# Microccontroller.net
KiCad netlist of a schematic drawn in Altium Designer
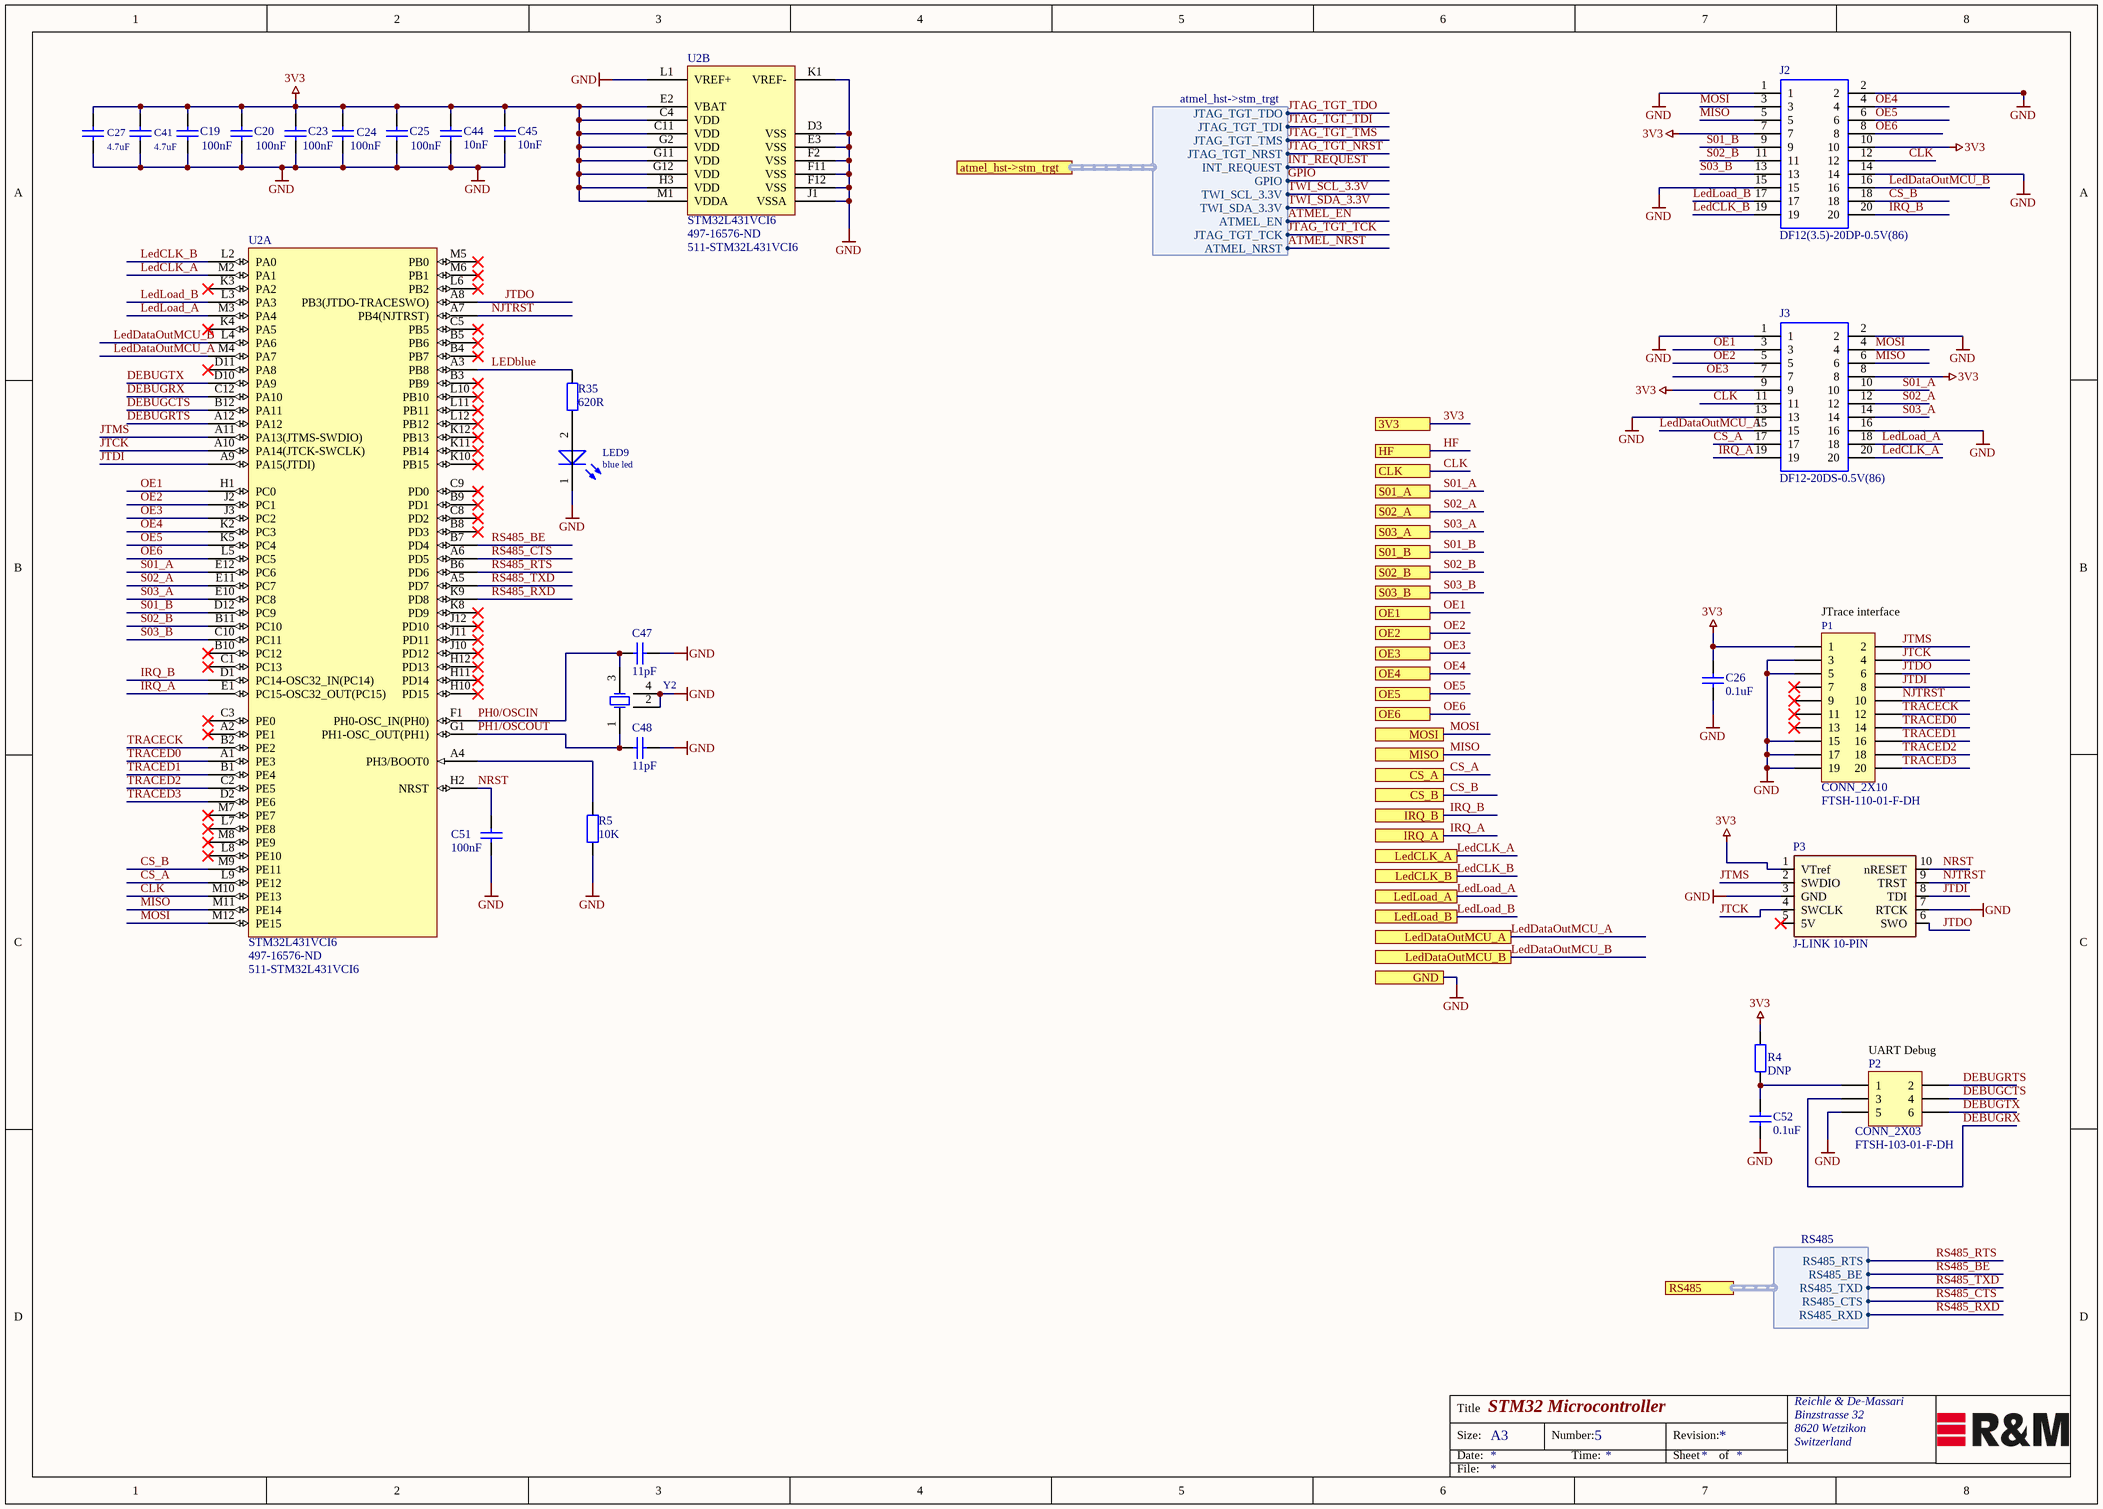
[diagram p0: Microccontroller.SchDoc]

(export (version "E")
  (design (tool "Eeschema 10.0.6"))
  (components
    (comp (ref "C19")
      (value "100nF")
      (footprint "CAPC0402(1005)60_L")
      (description "CAP 100nF 10V ±10% 0402 (1005 Metric) Thickness 0.6mm SMD")
      (fields (field (name "TOLERANCE") "Â±10%"))
      (libsource (lib "RDM_Altium_Library") (part "CAP 100nF 10V 0402(1005)"))
    )
    (comp (ref "C20")
      (value "100nF")
      (footprint "CAPC0402(1005)60_L")
      (description "CAP 100nF 10V ±10% 0402 (1005 Metric) Thickness 0.6mm SMD")
      (fields (field (name "TOLERANCE") "Â±10%"))
      (libsource (lib "RDM_Altium_Library") (part "CAP 100nF 10V 0402(1005)"))
    )
    (comp (ref "C23")
      (value "100nF")
      (footprint "CAPC0402(1005)60_L")
      (description "CAP 100nF 10V ±10% 0402 (1005 Metric) Thickness 0.6mm SMD")
      (fields (field (name "TOLERANCE") "Â±10%"))
      (libsource (lib "RDM_Altium_Library") (part "CAP 100nF 10V 0402(1005)"))
    )
    (comp (ref "C24")
      (value "100nF")
      (footprint "CAPC0402(1005)60_L")
      (description "CAP 100nF 10V ±10% 0402 (1005 Metric) Thickness 0.6mm SMD")
      (fields (field (name "TOLERANCE") "Â±10%"))
      (libsource (lib "RDM_Altium_Library") (part "CAP 100nF 10V 0402(1005)"))
    )
    (comp (ref "C25")
      (value "100nF")
      (footprint "CAPC0402(1005)60_L")
      (description "CAP 100nF 10V ±10% 0402 (1005 Metric) Thickness 0.6mm SMD")
      (fields (field (name "TOLERANCE") "Â±10%"))
      (libsource (lib "RDM_Altium_Library") (part "CAP 100nF 10V 0402(1005)"))
    )
    (comp (ref "C26")
      (value "0.1uF")
      (footprint "CAPC1005X55N")
      (description "SMD/SMT WCAP-CSGP 0.1uF 0402 20% 10V MLCC")
      (fields (field (name "TOLERANCE") "20%") (field (name "VOLTAGE") "10VDC"))
      (libsource (lib "RDM_Altium_Library") (part "Cap_0.1uF_0402"))
    )
    (comp (ref "C27")
      (value "4.7uF")
      (footprint "CAPC1005X55N")
      (description "4.7uF, Chip Monolithic Ceramic Condensators")
      (fields (field (name "MANUFACTURER") "Murata") (field (name "Comment") "DNP"))
      (libsource (lib "RDM_Altium_Library") (part "Cap_4.7uF_0402(1005)"))
    )
    (comp (ref "C41")
      (value "4.7uF")
      (footprint "CAP-0402[1005] - RFL")
      (description "4.7uF, Chip Monolithic Ceramic Condensators")
      (fields (field (name "MANUFACTURER") "Murata") (field (name "Comment") "GRM155R60J475ME47D"))
      (libsource (lib "RDM_Altium_Library") (part "Cap_4.7uF_0402(1005)"))
    )
    (comp (ref "C44")
      (value "10nF")
      (footprint "CAPC0402(1005)60_L")
      (description "CAP 10nF 10V ±10% 0402 (1005 Metric) Thickness 0.6mm SMD")
      (fields (field (name "TOLERANCE") "Â±10%"))
      (libsource (lib "RDM_Altium_Library") (part "CAP_10nf_10V_0402(1005)"))
    )
    (comp (ref "C45")
      (value "10nF")
      (footprint "CAPC0402(1005)60_L")
      (description "CAP 10nF 10V ±10% 0402 (1005 Metric) Thickness 0.6mm SMD")
      (fields (field (name "TOLERANCE") "Â±10%"))
      (libsource (lib "RDM_Altium_Library") (part "CAP_10nf_10V_0402(1005)"))
    )
    (comp (ref "C47")
      (value "11pF")
      (footprint "CAPC0402(1005)60_L")
      (description "CAP 11pF 10V ±0.25pF 0402 (1005 Metric) Thickness 0.6mm SMD")
      (fields (field (name "TOLERANCE") "Â±0.25pF"))
      (libsource (lib "RDM_Altium_Library") (part "CAP 11pF 10V 0402(1005)"))
    )
    (comp (ref "C48")
      (value "11pF")
      (footprint "CAPC0402(1005)60_L")
      (description "CAP 11pF 10V ±0.25pF 0402 (1005 Metric) Thickness 0.6mm SMD")
      (fields (field (name "TOLERANCE") "Â±0.25pF"))
      (libsource (lib "RDM_Altium_Library") (part "CAP 11pF 10V 0402(1005)"))
    )
    (comp (ref "C51")
      (value "100nF")
      (footprint "CAPC0402(1005)60_L")
      (description "CAP 100nF 10V ±10% 0402 (1005 Metric) Thickness 0.6mm SMD")
      (fields (field (name "TOLERANCE") "Â±10%"))
      (libsource (lib "RDM_Altium_Library") (part "CAP 100nF 10V 0402(1005)"))
    )
    (comp (ref "C52")
      (value "0.1uF")
      (footprint "Ceramic Capacitor 0402 EIA")
      (description "SMD/SMT WCAP-CSGP 0.1uF 0402 20% 10V MLCC")
      (fields (field (name "TOLERANCE") "20%") (field (name "VOLTAGE") "10VDC"))
      (libsource (lib "RDM_Altium_Library") (part "Cap_0.1uF_0402"))
    )
    (comp (ref "J2")
      (value "DF12(3.5)-20DP-0.5V(86)")
      (footprint "DF12(4.0)-20DP")
      (fields
        (field (name "MANUFACTURER") "Hirose")
        (field (name "RS PART NUMBER") "6082064P")
        (field (name "MOUSER PART NUMBER") "798-DF123520DP0.5V86")
      )
      (libsource (lib "RDM_Altium_Library") (part "DF12(3.5)-20DP-0.5V(86)"))
    )
    (comp (ref "J3")
      (value "DF12-20DS-0.5V(86)")
      (footprint "DF12-20DS")
      (fields
        (field (name "MANUFACTURER") "Hirose")
        (field (name "RS PART NUMBER") "1722478")
        (field (name "MOUSER PART NUMBER") "798-DF12-20DS-0.5V86")
      )
      (libsource (lib "RDM_Altium_Library") (part "DF12-20DS-0.5V(86)"))
    )
    (comp (ref "LED9")
      (value "blue led")
      (footprint "Kingbright_SMD_2_RWH")
      (description "blue, 1.6 x 0.6 mm Right Angle SMD Chip LED Lamp")
      (fields (field (name "MANUFACTURER") "Kingbright"))
      (libsource (lib "RDM_Altium_Library") (part "APA1606VBC/D"))
    )
    (comp (ref "P1")
      (value "CONN_2X10")
      (footprint "FTSH-110-01-F-DH")
      (description "20Pin, 2Rows, side/horizontally, MICRO LOW-PROFILE TERMINAL STRIPS")
      (fields (field (name "MANUFACTURER") "Samtec") (field (name "MANUFACTURER PARTNR") "FTSH-110-01-F-DH"))
      (libsource (lib "RDM_Altium_Library") (part "CONN_2X10_FTSH-110-01-F-DH"))
    )
    (comp (ref "P2")
      (value "CONN_2X03")
      (footprint "FTSH-103-01-F-DH")
      (description "6Pin, 2Rows, MICRO LOW-PROFILE TERMINAL STRIPS")
      (fields (field (name "MANUFACTURER") "Samtec") (field (name "MANUFACTURER PARTNR") "FTSH-103-01-F-DH"))
      (libsource (lib "RDM_Altium_Library") (part "CONN_2X03_FTSH-103-01-F-DH"))
    )
    (comp (ref "P3")
      (value "J-LINK 10-PIN")
      (footprint "CONN-SEGGER-10-PIN")
      (description "Segger, J-Link 10-pin Needle Adapter")
      (libsource (lib "RDM_ALT_SCH") (part "CONN_Segger_10_PIN"))
    )
    (comp (ref "R4")
      (value "DNP")
      (footprint "RESC1005X40N")
      (description "Resistor: do not populate")
      (fields (field (name "MANUFACTURER") "do not populate"))
      (libsource (lib "RDM_Altium_Library") (part "Res_DNP_0402"))
    )
    (comp (ref "R5")
      (value "10K")
      (footprint "RESC1005X40N")
      (description "10K 0.063W 1% 0402 (1005 Metric)  SMD")
      (libsource (lib "RDM_Altium_Library") (part "PassResBas0402-00623-A.3"))
    )
    (comp (ref "R35")
      (value "620R")
      (footprint "Resistor 0402 EIA")
      (description "SMD 1/16W 620ohm 0.5% 25ppm")
      (fields (field (name "TOLERANCE") "0.5%") (field (name "POWER") "62.5mW"))
      (libsource (lib "RDM_Altium_Library") (part "Res_620R_0402"))
    )
    (comp (ref "U2")
      (value "STM32L431VCI6")
      (footprint "STM_UFBGA100 7x7x0.6_100_R")
      (fields
        (field (name "MANUFACTURER") "STMicroelectronics")
        (field (name "SUPPLIER PART NUMBER 1") "497-16576-ND")
        (field (name "SUPPLIER PART NUMBER 2") "511-STM32L431VCI6")
      )
      (libsource (lib "RDM_Altium_Library") (part "STM32L431VCI6"))
    )
    (comp (ref "Y2")
      (value "ECS-160-10-36Q-ES-TR")
      (footprint "ECS_ECX-2236_4_R")
      (description "48MHz, SMD CRYSTAL")
      (fields (field (name "MANUFACTURER") "ECS"))
      (libsource (lib "RDM_Altium_Library") (part "CRYSTAL_4Pin_1_3"))
    )
  )
  (nets
    (net (code "5") (name "/CLK") (class "Default")
      (node (ref "J2") (pin "12") (pinfunction "12_12") (pintype "passive"))
      (node (ref "J3") (pin "11") (pinfunction "11_11") (pintype "passive"))
      (node (ref "U2") (pin "M10") (pinfunction "PE13_M10") (pintype "bidirectional"))
    )
    (net (code "6") (name "/CS_A") (class "Default")
      (node (ref "J3") (pin "17") (pinfunction "17_17") (pintype "passive"))
      (node (ref "U2") (pin "L9") (pinfunction "PE12_L9") (pintype "bidirectional"))
    )
    (net (code "7") (name "/CS_B") (class "Default")
      (node (ref "J2") (pin "18") (pinfunction "18_18") (pintype "passive"))
      (node (ref "U2") (pin "M9") (pinfunction "PE11_M9") (pintype "bidirectional"))
    )
    (net (code "8") (name "/DEBUGCTS") (class "Default")
      (node (ref "P2") (pin "4") (pinfunction "4_4") (pintype "passive"))
      (node (ref "U2") (pin "B12") (pinfunction "PA11_B12") (pintype "bidirectional"))
    )
    (net (code "9") (name "/DEBUGRTS") (class "Default")
      (node (ref "P2") (pin "2") (pinfunction "2_2") (pintype "passive"))
      (node (ref "U2") (pin "A12") (pinfunction "PA12_A12") (pintype "bidirectional"))
    )
    (net (code "10") (name "/DEBUGRX") (class "Default")
      (node (ref "P2") (pin "3") (pinfunction "3_3") (pintype "passive"))
      (node (ref "U2") (pin "C12") (pinfunction "PA10_C12") (pintype "bidirectional"))
    )
    (net (code "11") (name "/DEBUGTX") (class "Default")
      (node (ref "P2") (pin "6") (pinfunction "6_6") (pintype "passive"))
      (node (ref "U2") (pin "D10") (pinfunction "PA9_D10") (pintype "bidirectional"))
    )
    (net (code "15") (name "/IRQ_A") (class "Default")
      (node (ref "J3") (pin "19") (pinfunction "19_19") (pintype "passive"))
      (node (ref "U2") (pin "E1") (pinfunction "PC15-OSC32_OUT(PC15)_E1") (pintype "bidirectional"))
    )
    (net (code "16") (name "/IRQ_B") (class "Default")
      (node (ref "J2") (pin "20") (pinfunction "20_20") (pintype "passive"))
      (node (ref "U2") (pin "D1") (pinfunction "PC14-OSC32_IN(PC14)_D1") (pintype "bidirectional"))
    )
    (net (code "22") (name "/JTCK") (class "Default")
      (node (ref "P1") (pin "4") (pinfunction "4_4") (pintype "passive"))
      (node (ref "P3") (pin "4") (pinfunction "SWCLK_4") (pintype "passive"))
      (node (ref "U2") (pin "A10") (pinfunction "PA14(JTCK-SWCLK)_A10") (pintype "bidirectional"))
    )
    (net (code "23") (name "/JTDI") (class "Default")
      (node (ref "P1") (pin "8") (pinfunction "8_8") (pintype "passive"))
      (node (ref "P3") (pin "8") (pinfunction "TDI_8") (pintype "passive"))
      (node (ref "U2") (pin "A9") (pinfunction "PA15(JTDI)_A9") (pintype "bidirectional"))
    )
    (net (code "24") (name "/JTDO") (class "Default")
      (node (ref "P1") (pin "6") (pinfunction "6_6") (pintype "passive"))
      (node (ref "P3") (pin "6") (pinfunction "SWO_6") (pintype "passive"))
      (node (ref "U2") (pin "A8") (pinfunction "PB3(JTDO-TRACESWO)_A8") (pintype "bidirectional"))
    )
    (net (code "25") (name "/JTMS") (class "Default")
      (node (ref "P1") (pin "2") (pinfunction "2_2") (pintype "passive"))
      (node (ref "P3") (pin "2") (pinfunction "SWDIO_2") (pintype "passive"))
      (node (ref "U2") (pin "A11") (pinfunction "PA13(JTMS-SWDIO)_A11") (pintype "bidirectional"))
    )
    (net (code "26") (name "/LEDblue") (class "Default")
      (node (ref "R35") (pin "2") (pinfunction "2_2") (pintype "passive"))
      (node (ref "U2") (pin "A3") (pinfunction "PB8_A3") (pintype "bidirectional"))
    )
    (net (code "27") (name "/LedCLK_A") (class "Default")
      (node (ref "J3") (pin "20") (pinfunction "20_20") (pintype "passive"))
      (node (ref "U2") (pin "M2") (pinfunction "PA1_M2") (pintype "bidirectional"))
    )
    (net (code "28") (name "/LedCLK_B") (class "Default")
      (node (ref "J2") (pin "19") (pinfunction "19_19") (pintype "passive"))
      (node (ref "U2") (pin "L2") (pinfunction "PA0_L2") (pintype "bidirectional"))
    )
    (net (code "29") (name "/LedDataOutMCU_A") (class "Default")
      (node (ref "J3") (pin "15") (pinfunction "15_15") (pintype "passive"))
      (node (ref "U2") (pin "M4") (pinfunction "PA7_M4") (pintype "bidirectional"))
    )
    (net (code "30") (name "/LedDataOutMCU_B") (class "Default")
      (node (ref "J2") (pin "16") (pinfunction "16_16") (pintype "passive"))
      (node (ref "U2") (pin "L4") (pinfunction "PA6_L4") (pintype "bidirectional"))
    )
    (net (code "31") (name "/LedLoad_A") (class "Default")
      (node (ref "J3") (pin "18") (pinfunction "18_18") (pintype "passive"))
      (node (ref "U2") (pin "M3") (pinfunction "PA4_M3") (pintype "bidirectional"))
    )
    (net (code "32") (name "/LedLoad_B") (class "Default")
      (node (ref "J2") (pin "17") (pinfunction "17_17") (pintype "passive"))
      (node (ref "U2") (pin "L3") (pinfunction "PA3_L3") (pintype "bidirectional"))
    )
    (net (code "33") (name "/MISO") (class "Default")
      (node (ref "J2") (pin "5") (pinfunction "5_5") (pintype "passive"))
      (node (ref "J3") (pin "6") (pinfunction "6_6") (pintype "passive"))
      (node (ref "U2") (pin "M11") (pinfunction "PE14_M11") (pintype "bidirectional"))
    )
    (net (code "34") (name "/MOSI") (class "Default")
      (node (ref "J2") (pin "3") (pinfunction "3_3") (pintype "passive"))
      (node (ref "J3") (pin "4") (pinfunction "4_4") (pintype "passive"))
      (node (ref "U2") (pin "M12") (pinfunction "PE15_M12") (pintype "bidirectional"))
    )
    (net (code "35") (name "/NJTRST") (class "Default")
      (node (ref "P1") (pin "10") (pinfunction "10_10") (pintype "passive"))
      (node (ref "P3") (pin "9") (pinfunction "TRST_9") (pintype "passive"))
      (node (ref "U2") (pin "A7") (pinfunction "PB4(NJTRST)_A7") (pintype "bidirectional"))
    )
    (net (code "36") (name "/NRST") (class "Default")
      (node (ref "C51") (pin "2") (pinfunction "2_2") (pintype "passive"))
      (node (ref "P3") (pin "10") (pinfunction "nRESET_10") (pintype "passive"))
      (node (ref "U2") (pin "H2") (pinfunction "NRST_H2") (pintype "bidirectional"))
    )
    (net (code "37") (name "/OE1") (class "Default")
      (node (ref "J3") (pin "3") (pinfunction "3_3") (pintype "passive"))
      (node (ref "U2") (pin "H1") (pinfunction "PC0_H1") (pintype "bidirectional"))
    )
    (net (code "38") (name "/OE2") (class "Default")
      (node (ref "J3") (pin "5") (pinfunction "5_5") (pintype "passive"))
      (node (ref "U2") (pin "J2") (pinfunction "PC1_J2") (pintype "bidirectional"))
    )
    (net (code "39") (name "/OE3") (class "Default")
      (node (ref "J3") (pin "7") (pinfunction "7_7") (pintype "passive"))
      (node (ref "U2") (pin "J3") (pinfunction "PC2_J3") (pintype "bidirectional"))
    )
    (net (code "40") (name "/OE4") (class "Default")
      (node (ref "J2") (pin "4") (pinfunction "4_4") (pintype "passive"))
      (node (ref "U2") (pin "K2") (pinfunction "PC3_K2") (pintype "bidirectional"))
    )
    (net (code "41") (name "/OE5") (class "Default")
      (node (ref "J2") (pin "6") (pinfunction "6_6") (pintype "passive"))
      (node (ref "U2") (pin "K5") (pinfunction "PC4_K5") (pintype "bidirectional"))
    )
    (net (code "42") (name "/OE6") (class "Default")
      (node (ref "J2") (pin "8") (pinfunction "8_8") (pintype "passive"))
      (node (ref "U2") (pin "L5") (pinfunction "PC5_L5") (pintype "bidirectional"))
    )
    (net (code "43") (name "/PH0{slash}OSCIN") (class "Default")
      (node (ref "C47") (pin "1") (pinfunction "1_1") (pintype "passive"))
      (node (ref "U2") (pin "F1") (pinfunction "PH0-OSC_IN(PH0)_F1") (pintype "bidirectional"))
      (node (ref "Y2") (pin "3") (pinfunction "OSC2_3") (pintype "passive"))
    )
    (net (code "44") (name "/PH1{slash}OSCOUT") (class "Default")
      (node (ref "C48") (pin "1") (pinfunction "1_1") (pintype "passive"))
      (node (ref "U2") (pin "G1") (pinfunction "PH1-OSC_OUT(PH1)_G1") (pintype "bidirectional"))
      (node (ref "Y2") (pin "1") (pinfunction "OSC1_1") (pintype "passive"))
    )
    (net (code "45") (name "/RS485_BE") (class "Default")
      (node (ref "U2") (pin "B7") (pinfunction "PD4_B7") (pintype "bidirectional"))
    )
    (net (code "46") (name "/RS485_CTS") (class "Default")
      (node (ref "U2") (pin "A6") (pinfunction "PD5_A6") (pintype "bidirectional"))
    )
    (net (code "47") (name "/RS485_RTS") (class "Default")
      (node (ref "U2") (pin "B6") (pinfunction "PD6_B6") (pintype "bidirectional"))
    )
    (net (code "48") (name "/RS485_RXD") (class "Default")
      (node (ref "U2") (pin "K9") (pinfunction "PD8_K9") (pintype "bidirectional"))
    )
    (net (code "49") (name "/RS485_TXD") (class "Default")
      (node (ref "U2") (pin "A5") (pinfunction "PD7_A5") (pintype "bidirectional"))
    )
    (net (code "50") (name "/S01_A") (class "Default")
      (node (ref "J3") (pin "10") (pinfunction "10_10") (pintype "passive"))
      (node (ref "U2") (pin "E12") (pinfunction "PC6_E12") (pintype "bidirectional"))
    )
    (net (code "51") (name "/S01_B") (class "Default")
      (node (ref "J2") (pin "9") (pinfunction "9_9") (pintype "passive"))
      (node (ref "U2") (pin "D12") (pinfunction "PC9_D12") (pintype "bidirectional"))
    )
    (net (code "52") (name "/S02_A") (class "Default")
      (node (ref "J3") (pin "12") (pinfunction "12_12") (pintype "passive"))
      (node (ref "U2") (pin "E11") (pinfunction "PC7_E11") (pintype "bidirectional"))
    )
    (net (code "53") (name "/S02_B") (class "Default")
      (node (ref "J2") (pin "11") (pinfunction "11_11") (pintype "passive"))
      (node (ref "U2") (pin "B11") (pinfunction "PC10_B11") (pintype "bidirectional"))
    )
    (net (code "54") (name "/S03_A") (class "Default")
      (node (ref "J3") (pin "14") (pinfunction "14_14") (pintype "passive"))
      (node (ref "U2") (pin "E10") (pinfunction "PC8_E10") (pintype "bidirectional"))
    )
    (net (code "55") (name "/S03_B") (class "Default")
      (node (ref "J2") (pin "13") (pinfunction "13_13") (pintype "passive"))
      (node (ref "U2") (pin "C10") (pinfunction "PC11_C10") (pintype "bidirectional"))
    )
    (net (code "56") (name "/TRACECK") (class "Default")
      (node (ref "P1") (pin "12") (pinfunction "12_12") (pintype "passive"))
      (node (ref "U2") (pin "B2") (pinfunction "PE2_B2") (pintype "bidirectional"))
    )
    (net (code "57") (name "/TRACED0") (class "Default")
      (node (ref "P1") (pin "14") (pinfunction "14_14") (pintype "passive"))
      (node (ref "U2") (pin "A1") (pinfunction "PE3_A1") (pintype "bidirectional"))
    )
    (net (code "58") (name "/TRACED1") (class "Default")
      (node (ref "P1") (pin "16") (pinfunction "16_16") (pintype "passive"))
      (node (ref "U2") (pin "B1") (pinfunction "PE4_B1") (pintype "bidirectional"))
    )
    (net (code "59") (name "/TRACED2") (class "Default")
      (node (ref "P1") (pin "18") (pinfunction "18_18") (pintype "passive"))
      (node (ref "U2") (pin "C2") (pinfunction "PE5_C2") (pintype "bidirectional"))
    )
    (net (code "60") (name "/TRACED3") (class "Default")
      (node (ref "P1") (pin "20") (pinfunction "20_20") (pintype "passive"))
      (node (ref "U2") (pin "D2") (pinfunction "PE6_D2") (pintype "bidirectional"))
    )
    (net (code "65") (name "3V3") (class "Default")
      (node (ref "C19") (pin "2") (pinfunction "2_2") (pintype "passive"))
      (node (ref "C20") (pin "2") (pinfunction "2_2") (pintype "passive"))
      (node (ref "C23") (pin "2") (pinfunction "2_2") (pintype "passive"))
      (node (ref "C24") (pin "2") (pinfunction "2_2") (pintype "passive"))
      (node (ref "C25") (pin "2") (pinfunction "2_2") (pintype "passive"))
      (node (ref "C26") (pin "2") (pinfunction "2_2") (pintype "passive"))
      (node (ref "C27") (pin "1") (pinfunction "Pos_1") (pintype "passive"))
      (node (ref "C41") (pin "1") (pinfunction "Pos_1") (pintype "passive"))
      (node (ref "C44") (pin "2") (pinfunction "2_2") (pintype "passive"))
      (node (ref "C45") (pin "2") (pinfunction "2_2") (pintype "passive"))
      (node (ref "J2") (pin "10") (pinfunction "10_10") (pintype "passive"))
      (node (ref "J2") (pin "7") (pinfunction "7_7") (pintype "passive"))
      (node (ref "J3") (pin "8") (pinfunction "8_8") (pintype "passive"))
      (node (ref "J3") (pin "9") (pinfunction "9_9") (pintype "passive"))
      (node (ref "P1") (pin "1") (pinfunction "1_1") (pintype "passive"))
      (node (ref "P3") (pin "1") (pinfunction "VTref_1") (pintype "passive"))
      (node (ref "R4") (pin "2") (pinfunction "2_2") (pintype "passive"))
      (node (ref "U2") (pin "C11") (pinfunction "VDD_C11") (pintype "power_in"))
      (node (ref "U2") (pin "C4") (pinfunction "VDD_C4") (pintype "power_in"))
      (node (ref "U2") (pin "E2") (pinfunction "VBAT_E2") (pintype "power_in"))
      (node (ref "U2") (pin "G11") (pinfunction "VDD_G11") (pintype "power_in"))
      (node (ref "U2") (pin "G12") (pinfunction "VDD_G12") (pintype "power_in"))
      (node (ref "U2") (pin "G2") (pinfunction "VDD_G2") (pintype "power_in"))
      (node (ref "U2") (pin "H3") (pinfunction "VDD_H3") (pintype "power_in"))
      (node (ref "U2") (pin "M1") (pinfunction "VDDA_M1") (pintype "power_in"))
    )
    (net (code "66") (name "GND") (class "Default")
      (node (ref "C19") (pin "1") (pinfunction "1_1") (pintype "passive"))
      (node (ref "C20") (pin "1") (pinfunction "1_1") (pintype "passive"))
      (node (ref "C23") (pin "1") (pinfunction "1_1") (pintype "passive"))
      (node (ref "C24") (pin "1") (pinfunction "1_1") (pintype "passive"))
      (node (ref "C25") (pin "1") (pinfunction "1_1") (pintype "passive"))
      (node (ref "C26") (pin "1") (pinfunction "1_1") (pintype "passive"))
      (node (ref "C27") (pin "2") (pinfunction "Neg_2") (pintype "passive"))
      (node (ref "C41") (pin "2") (pinfunction "Neg_2") (pintype "passive"))
      (node (ref "C44") (pin "1") (pinfunction "1_1") (pintype "passive"))
      (node (ref "C45") (pin "1") (pinfunction "1_1") (pintype "passive"))
      (node (ref "C47") (pin "2") (pinfunction "2_2") (pintype "passive"))
      (node (ref "C48") (pin "2") (pinfunction "2_2") (pintype "passive"))
      (node (ref "C51") (pin "1") (pinfunction "1_1") (pintype "passive"))
      (node (ref "C52") (pin "1") (pinfunction "1_1") (pintype "passive"))
      (node (ref "J2") (pin "1") (pinfunction "1_1") (pintype "passive"))
      (node (ref "J2") (pin "14") (pinfunction "14_14") (pintype "passive"))
      (node (ref "J2") (pin "15") (pinfunction "15_15") (pintype "passive"))
      (node (ref "J2") (pin "2") (pinfunction "2_2") (pintype "passive"))
      (node (ref "J3") (pin "1") (pinfunction "1_1") (pintype "passive"))
      (node (ref "J3") (pin "13") (pinfunction "13_13") (pintype "passive"))
      (node (ref "J3") (pin "16") (pinfunction "16_16") (pintype "passive"))
      (node (ref "J3") (pin "2") (pinfunction "2_2") (pintype "passive"))
      (node (ref "LED9") (pin "1") (pinfunction "K_1") (pintype "passive"))
      (node (ref "P1") (pin "15") (pinfunction "15_15") (pintype "passive"))
      (node (ref "P1") (pin "17") (pinfunction "17_17") (pintype "passive"))
      (node (ref "P1") (pin "19") (pinfunction "19_19") (pintype "passive"))
      (node (ref "P1") (pin "3") (pinfunction "3_3") (pintype "passive"))
      (node (ref "P1") (pin "5") (pinfunction "5_5") (pintype "passive"))
      (node (ref "P2") (pin "5") (pinfunction "5_5") (pintype "passive"))
      (node (ref "P3") (pin "3") (pinfunction "GND_3") (pintype "passive"))
      (node (ref "P3") (pin "7") (pinfunction "RTCK_7") (pintype "passive"))
      (node (ref "R5") (pin "2") (pinfunction "2_2") (pintype "passive"))
      (node (ref "U2") (pin "D3") (pinfunction "VSS_D3") (pintype "power_in"))
      (node (ref "U2") (pin "E3") (pinfunction "VSS_E3") (pintype "power_in"))
      (node (ref "U2") (pin "F11") (pinfunction "VSS_F11") (pintype "power_in"))
      (node (ref "U2") (pin "F12") (pinfunction "VSS_F12") (pintype "power_in"))
      (node (ref "U2") (pin "F2") (pinfunction "VSS_F2") (pintype "power_in"))
      (node (ref "U2") (pin "J1") (pinfunction "VSSA_J1") (pintype "power_in"))
      (node (ref "U2") (pin "K1") (pinfunction "VREF-_K1") (pintype "power_in"))
      (node (ref "U2") (pin "L1") (pinfunction "VREF+_L1") (pintype "power_in"))
      (node (ref "Y2") (pin "2") (pinfunction "OSC2_2") (pintype "passive"))
      (node (ref "Y2") (pin "4") (pinfunction "OSC3_4") (pintype "passive"))
    )
    (net (code "67") (name "Net-(C52-Pad2)") (class "Default")
      (node (ref "C52") (pin "2") (pinfunction "2_2") (pintype "passive"))
      (node (ref "P2") (pin "1") (pinfunction "1_1") (pintype "passive"))
      (node (ref "R4") (pin "1") (pinfunction "1_1") (pintype "passive"))
    )
    (net (code "68") (name "Net-(LED9-A)") (class "Default")
      (node (ref "LED9") (pin "2") (pinfunction "A_2") (pintype "passive"))
      (node (ref "R35") (pin "1") (pinfunction "1_1") (pintype "passive"))
    )
    (net (code "69") (name "Net-(U2A-PH3{slash}BOOT0)") (class "Default")
      (node (ref "R5") (pin "1") (pinfunction "1_1") (pintype "passive"))
      (node (ref "U2") (pin "A4") (pinfunction "PH3/BOOT0_A4") (pintype "input"))
    )
    (net (code "70") (name "unconnected-(P1-Pad7)") (class "Default")
      (node (ref "P1") (pin "7") (pinfunction "7_7") (pintype "passive+no_connect"))
    )
    (net (code "71") (name "unconnected-(P1-Pad9)") (class "Default")
      (node (ref "P1") (pin "9") (pinfunction "9_9") (pintype "passive+no_connect"))
    )
    (net (code "72") (name "unconnected-(P1-Pad11)") (class "Default")
      (node (ref "P1") (pin "11") (pinfunction "11_11") (pintype "passive+no_connect"))
    )
    (net (code "73") (name "unconnected-(P1-Pad13)") (class "Default")
      (node (ref "P1") (pin "13") (pinfunction "13_13") (pintype "passive+no_connect"))
    )
    (net (code "74") (name "unconnected-(P3-5V-Pad5)") (class "Default")
      (node (ref "P3") (pin "5") (pinfunction "5V_5") (pintype "passive+no_connect"))
    )
    (net (code "75") (name "unconnected-(U2A-PA2-PadK3)") (class "Default")
      (node (ref "U2") (pin "K3") (pinfunction "PA2_K3") (pintype "bidirectional+no_connect"))
    )
    (net (code "76") (name "unconnected-(U2A-PA5-PadK4)") (class "Default")
      (node (ref "U2") (pin "K4") (pinfunction "PA5_K4") (pintype "bidirectional+no_connect"))
    )
    (net (code "77") (name "unconnected-(U2A-PA8-PadD11)") (class "Default")
      (node (ref "U2") (pin "D11") (pinfunction "PA8_D11") (pintype "bidirectional+no_connect"))
    )
    (net (code "78") (name "unconnected-(U2A-PB0-PadM5)") (class "Default")
      (node (ref "U2") (pin "M5") (pinfunction "PB0_M5") (pintype "bidirectional+no_connect"))
    )
    (net (code "79") (name "unconnected-(U2A-PB1-PadM6)") (class "Default")
      (node (ref "U2") (pin "M6") (pinfunction "PB1_M6") (pintype "bidirectional+no_connect"))
    )
    (net (code "80") (name "unconnected-(U2A-PB2-PadL6)") (class "Default")
      (node (ref "U2") (pin "L6") (pinfunction "PB2_L6") (pintype "bidirectional+no_connect"))
    )
    (net (code "81") (name "unconnected-(U2A-PB5-PadC5)") (class "Default")
      (node (ref "U2") (pin "C5") (pinfunction "PB5_C5") (pintype "bidirectional+no_connect"))
    )
    (net (code "82") (name "unconnected-(U2A-PB6-PadB5)") (class "Default")
      (node (ref "U2") (pin "B5") (pinfunction "PB6_B5") (pintype "bidirectional+no_connect"))
    )
    (net (code "83") (name "unconnected-(U2A-PB7-PadB4)") (class "Default")
      (node (ref "U2") (pin "B4") (pinfunction "PB7_B4") (pintype "bidirectional+no_connect"))
    )
    (net (code "84") (name "unconnected-(U2A-PB9-PadB3)") (class "Default")
      (node (ref "U2") (pin "B3") (pinfunction "PB9_B3") (pintype "bidirectional+no_connect"))
    )
    (net (code "85") (name "unconnected-(U2A-PB10-PadL10)") (class "Default")
      (node (ref "U2") (pin "L10") (pinfunction "PB10_L10") (pintype "bidirectional+no_connect"))
    )
    (net (code "86") (name "unconnected-(U2A-PB11-PadL11)") (class "Default")
      (node (ref "U2") (pin "L11") (pinfunction "PB11_L11") (pintype "bidirectional+no_connect"))
    )
    (net (code "87") (name "unconnected-(U2A-PB12-PadL12)") (class "Default")
      (node (ref "U2") (pin "L12") (pinfunction "PB12_L12") (pintype "bidirectional+no_connect"))
    )
    (net (code "88") (name "unconnected-(U2A-PB13-PadK12)") (class "Default")
      (node (ref "U2") (pin "K12") (pinfunction "PB13_K12") (pintype "bidirectional+no_connect"))
    )
    (net (code "89") (name "unconnected-(U2A-PB14-PadK11)") (class "Default")
      (node (ref "U2") (pin "K11") (pinfunction "PB14_K11") (pintype "bidirectional+no_connect"))
    )
    (net (code "90") (name "unconnected-(U2A-PB15-PadK10)") (class "Default")
      (node (ref "U2") (pin "K10") (pinfunction "PB15_K10") (pintype "bidirectional+no_connect"))
    )
    (net (code "91") (name "unconnected-(U2A-PC12-PadB10)") (class "Default")
      (node (ref "U2") (pin "B10") (pinfunction "PC12_B10") (pintype "bidirectional+no_connect"))
    )
    (net (code "92") (name "unconnected-(U2A-PC13-PadC1)") (class "Default")
      (node (ref "U2") (pin "C1") (pinfunction "PC13_C1") (pintype "bidirectional+no_connect"))
    )
    (net (code "93") (name "unconnected-(U2A-PD0-PadC9)") (class "Default")
      (node (ref "U2") (pin "C9") (pinfunction "PD0_C9") (pintype "bidirectional+no_connect"))
    )
    (net (code "94") (name "unconnected-(U2A-PD1-PadB9)") (class "Default")
      (node (ref "U2") (pin "B9") (pinfunction "PD1_B9") (pintype "bidirectional+no_connect"))
    )
    (net (code "95") (name "unconnected-(U2A-PD2-PadC8)") (class "Default")
      (node (ref "U2") (pin "C8") (pinfunction "PD2_C8") (pintype "bidirectional+no_connect"))
    )
    (net (code "96") (name "unconnected-(U2A-PD3-PadB8)") (class "Default")
      (node (ref "U2") (pin "B8") (pinfunction "PD3_B8") (pintype "bidirectional+no_connect"))
    )
    (net (code "97") (name "unconnected-(U2A-PD9-PadK8)") (class "Default")
      (node (ref "U2") (pin "K8") (pinfunction "PD9_K8") (pintype "bidirectional+no_connect"))
    )
    (net (code "98") (name "unconnected-(U2A-PD10-PadJ12)") (class "Default")
      (node (ref "U2") (pin "J12") (pinfunction "PD10_J12") (pintype "bidirectional+no_connect"))
    )
    (net (code "99") (name "unconnected-(U2A-PD11-PadJ11)") (class "Default")
      (node (ref "U2") (pin "J11") (pinfunction "PD11_J11") (pintype "bidirectional+no_connect"))
    )
    (net (code "100") (name "unconnected-(U2A-PD12-PadJ10)") (class "Default")
      (node (ref "U2") (pin "J10") (pinfunction "PD12_J10") (pintype "bidirectional+no_connect"))
    )
    (net (code "101") (name "unconnected-(U2A-PD13-PadH12)") (class "Default")
      (node (ref "U2") (pin "H12") (pinfunction "PD13_H12") (pintype "bidirectional+no_connect"))
    )
    (net (code "102") (name "unconnected-(U2A-PD14-PadH11)") (class "Default")
      (node (ref "U2") (pin "H11") (pinfunction "PD14_H11") (pintype "bidirectional+no_connect"))
    )
    (net (code "103") (name "unconnected-(U2A-PD15-PadH10)") (class "Default")
      (node (ref "U2") (pin "H10") (pinfunction "PD15_H10") (pintype "bidirectional+no_connect"))
    )
    (net (code "104") (name "unconnected-(U2A-PE0-PadC3)") (class "Default")
      (node (ref "U2") (pin "C3") (pinfunction "PE0_C3") (pintype "bidirectional+no_connect"))
    )
    (net (code "105") (name "unconnected-(U2A-PE1-PadA2)") (class "Default")
      (node (ref "U2") (pin "A2") (pinfunction "PE1_A2") (pintype "bidirectional+no_connect"))
    )
    (net (code "106") (name "unconnected-(U2A-PE7-PadM7)") (class "Default")
      (node (ref "U2") (pin "M7") (pinfunction "PE7_M7") (pintype "bidirectional+no_connect"))
    )
    (net (code "107") (name "unconnected-(U2A-PE8-PadL7)") (class "Default")
      (node (ref "U2") (pin "L7") (pinfunction "PE8_L7") (pintype "bidirectional+no_connect"))
    )
    (net (code "108") (name "unconnected-(U2A-PE9-PadM8)") (class "Default")
      (node (ref "U2") (pin "M8") (pinfunction "PE9_M8") (pintype "bidirectional+no_connect"))
    )
    (net (code "109") (name "unconnected-(U2A-PE10-PadL8)") (class "Default")
      (node (ref "U2") (pin "L8") (pinfunction "PE10_L8") (pintype "bidirectional+no_connect"))
    )
  )
)
